# Part3_3210105209.net
KiCad netlist of a schematic drawn in Altium Designer
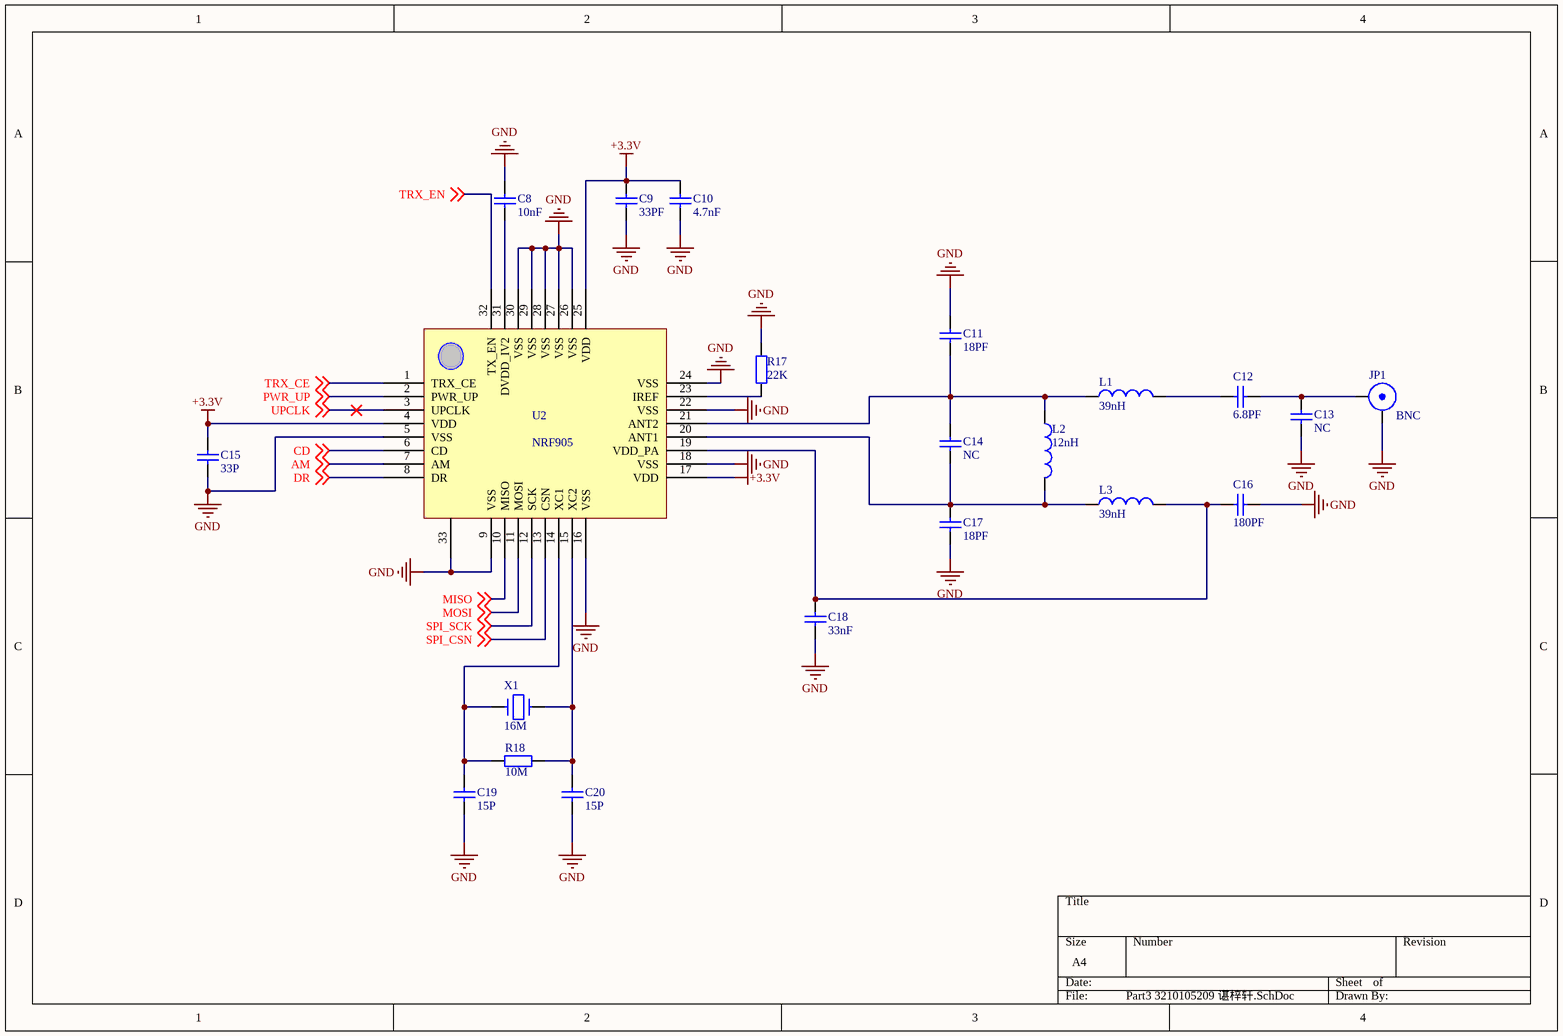
[diagram p0: Part3 3210105209 谌梓轩.SchDoc]

(export (version "E")
  (design (tool "Eeschema 10.0.6"))
  (components
    (comp (ref "C8")
      (value "10nF")
      (footprint "0603C")
      (description "Capacitor")
      (fields (field (name "PUBLISHER") "Altium Limited"))
      (libsource (lib "ECG2.0_1") (part "Cap"))
    )
    (comp (ref "C9")
      (value "33PF")
      (footprint "0603C")
      (description "Capacitor")
      (fields (field (name "PUBLISHER") "Altium Limited"))
      (libsource (lib "ECG2.0_1") (part "Cap"))
    )
    (comp (ref "C10")
      (value "4.7nF")
      (footprint "0603C")
      (description "Capacitor")
      (fields (field (name "PUBLISHER") "Altium Limited"))
      (libsource (lib "ECG2.0_1") (part "Cap"))
    )
    (comp (ref "C11")
      (value "18PF")
      (footprint "0603C")
      (description "Capacitor")
      (fields (field (name "PUBLISHER") "Altium Limited"))
      (libsource (lib "ECG2.0_1") (part "Cap"))
    )
    (comp (ref "C12")
      (value "6.8PF")
      (footprint "0603C")
      (description "Capacitor")
      (fields (field (name "PUBLISHER") "Altium Limited"))
      (libsource (lib "ECG2.0_1") (part "Cap"))
    )
    (comp (ref "C13")
      (value "NC")
      (footprint "0603C")
      (description "Capacitor")
      (fields (field (name "PUBLISHER") "Altium Limited"))
      (libsource (lib "ECG2.0_1") (part "Cap"))
    )
    (comp (ref "C14")
      (value "NC")
      (footprint "0603C")
      (description "Capacitor")
      (fields (field (name "PUBLISHER") "Altium Limited"))
      (libsource (lib "ECG2.0_1") (part "Cap"))
    )
    (comp (ref "C15")
      (value "33P")
      (footprint "0603C")
      (description "Capacitor")
      (fields (field (name "PUBLISHER") "Altium Limited"))
      (libsource (lib "ECG2.0_1") (part "Cap"))
    )
    (comp (ref "C16")
      (value "180PF")
      (footprint "0603C")
      (description "Capacitor")
      (fields (field (name "PUBLISHER") "Altium Limited"))
      (libsource (lib "ECG2.0_1") (part "Cap"))
    )
    (comp (ref "C17")
      (value "18PF")
      (footprint "0603C")
      (description "Capacitor")
      (fields (field (name "PUBLISHER") "Altium Limited"))
      (libsource (lib "ECG2.0_1") (part "Cap"))
    )
    (comp (ref "C18")
      (value "33nF")
      (footprint "0603C")
      (description "Capacitor")
      (fields (field (name "PUBLISHER") "Altium Limited"))
      (libsource (lib "ECG2.0_1") (part "Cap"))
    )
    (comp (ref "C19")
      (value "15P")
      (footprint "0603C")
      (description "Capacitor")
      (fields (field (name "PUBLISHER") "Altium Limited"))
      (libsource (lib "ECG2.0_1") (part "Cap"))
    )
    (comp (ref "C20")
      (value "15P")
      (footprint "0603C")
      (description "Capacitor")
      (fields (field (name "PUBLISHER") "Altium Limited"))
      (libsource (lib "ECG2.0_1") (part "Cap"))
    )
    (comp (ref "JP1") (value "BNC") (footprint "SMA") (libsource (lib "ECG2.0_1") (part "BNC")))
    (comp (ref "L1") (value "39nH") (footprint "0603-D") (libsource (lib "ECG2.0_1") (part "INDUCTOR")))
    (comp (ref "L2") (value "12nH") (footprint "0603-D") (libsource (lib "ECG2.0_1") (part "INDUCTOR")))
    (comp (ref "L3") (value "39nH") (footprint "0603-D") (libsource (lib "ECG2.0_1") (part "INDUCTOR")))
    (comp (ref "R17")
      (value "22K")
      (footprint "0603R")
      (description "Resistor")
      (fields (field (name "PUBLISHER") "Altium Limited"))
      (libsource (lib "ECG2.0_1") (part "Res2"))
    )
    (comp (ref "R18")
      (value "10M")
      (footprint "0603R")
      (description "Resistor")
      (fields (field (name "PUBLISHER") "Altium Limited"))
      (libsource (lib "") (part "Res2_1"))
    )
    (comp (ref "U2")
      (value "NRF905")
      (footprint "QFN32_M")
      (libsource (lib "ECG2.0_1") (part "Component_1_1"))
    )
    (comp (ref "X1") (value "16M") (footprint "CY2") (libsource (lib "ECG2.0_1") (part "CRYSTAL")))
  )
  (nets
    (net (code "1") (name "+3.3V") (class "Default")
      (node (ref "C10") (pin "2") (pinfunction "2_2") (pintype "passive"))
      (node (ref "C15") (pin "2") (pinfunction "2_2") (pintype "passive"))
      (node (ref "C9") (pin "2") (pinfunction "2_2") (pintype "passive"))
      (node (ref "U2") (pin "17") (pinfunction "VDD_17") (pintype "passive"))
      (node (ref "U2") (pin "25") (pinfunction "VDD_25") (pintype "passive"))
      (node (ref "U2") (pin "4") (pinfunction "VDD_4") (pintype "passive"))
    )
    (net (code "2") (name "AM") (class "Default")
      (node (ref "U2") (pin "7") (pinfunction "AM_7") (pintype "passive"))
    )
    (net (code "3") (name "CD") (class "Default")
      (node (ref "U2") (pin "6") (pinfunction "CD_6") (pintype "passive"))
    )
    (net (code "4") (name "DR") (class "Default")
      (node (ref "U2") (pin "8") (pinfunction "DR_8") (pintype "passive"))
    )
    (net (code "5") (name "GND") (class "Default")
      (node (ref "C10") (pin "1") (pinfunction "1_1") (pintype "passive"))
      (node (ref "C11") (pin "2") (pinfunction "2_2") (pintype "passive"))
      (node (ref "C13") (pin "1") (pinfunction "1_1") (pintype "passive"))
      (node (ref "C15") (pin "1") (pinfunction "1_1") (pintype "passive"))
      (node (ref "C16") (pin "2") (pinfunction "2_2") (pintype "passive"))
      (node (ref "C17") (pin "1") (pinfunction "1_1") (pintype "passive"))
      (node (ref "C18") (pin "1") (pinfunction "1_1") (pintype "passive"))
      (node (ref "C19") (pin "1") (pinfunction "1_1") (pintype "passive"))
      (node (ref "C20") (pin "1") (pinfunction "1_1") (pintype "passive"))
      (node (ref "C8") (pin "2") (pinfunction "2_2") (pintype "passive"))
      (node (ref "C9") (pin "1") (pinfunction "1_1") (pintype "passive"))
      (node (ref "JP1") (pin "1") (pintype "passive"))
      (node (ref "R17") (pin "2") (pinfunction "2_2") (pintype "passive"))
      (node (ref "U2") (pin "16") (pinfunction "VSS_16") (pintype "passive"))
      (node (ref "U2") (pin "18") (pinfunction "VSS_18") (pintype "passive"))
      (node (ref "U2") (pin "22") (pinfunction "VSS_22") (pintype "passive"))
      (node (ref "U2") (pin "24") (pinfunction "VSS_24") (pintype "passive"))
      (node (ref "U2") (pin "26") (pinfunction "VSS_26") (pintype "passive"))
      (node (ref "U2") (pin "27") (pinfunction "VSS_27") (pintype "passive"))
      (node (ref "U2") (pin "28") (pinfunction "VSS_28") (pintype "passive"))
      (node (ref "U2") (pin "29") (pinfunction "VSS_29") (pintype "passive"))
      (node (ref "U2") (pin "30") (pinfunction "VSS_30") (pintype "passive"))
      (node (ref "U2") (pin "33") (pinfunction "33_33") (pintype "passive"))
      (node (ref "U2") (pin "5") (pinfunction "VSS_5") (pintype "passive"))
      (node (ref "U2") (pin "9") (pinfunction "VSS_9") (pintype "passive"))
    )
    (net (code "6") (name "MISO") (class "Default")
      (node (ref "U2") (pin "10") (pinfunction "MISO_10") (pintype "passive"))
    )
    (net (code "7") (name "MOSI") (class "Default")
      (node (ref "U2") (pin "11") (pinfunction "MOSI_11") (pintype "passive"))
    )
    (net (code "8") (name "Net-(C12-Pad1)") (class "Default")
      (node (ref "C12") (pin "1") (pinfunction "1_1") (pintype "passive"))
      (node (ref "L1") (pin "2") (pinfunction "2_2") (pintype "passive"))
    )
    (net (code "9") (name "Net-(C12-Pad2)") (class "Default")
      (node (ref "C12") (pin "2") (pinfunction "2_2") (pintype "passive"))
      (node (ref "C13") (pin "2") (pinfunction "2_2") (pintype "passive"))
      (node (ref "JP1") (pin "2") (pintype "passive"))
    )
    (net (code "10") (name "Net-(U2-ANT1)") (class "Default")
      (node (ref "C14") (pin "1") (pinfunction "1_1") (pintype "passive"))
      (node (ref "C17") (pin "2") (pinfunction "2_2") (pintype "passive"))
      (node (ref "L2") (pin "2") (pinfunction "2_2") (pintype "passive"))
      (node (ref "L3") (pin "1") (pinfunction "1_1") (pintype "passive"))
      (node (ref "U2") (pin "20") (pinfunction "ANT1_20") (pintype "passive"))
    )
    (net (code "11") (name "Net-(U2-ANT2)") (class "Default")
      (node (ref "C11") (pin "1") (pinfunction "1_1") (pintype "passive"))
      (node (ref "C14") (pin "2") (pinfunction "2_2") (pintype "passive"))
      (node (ref "L1") (pin "1") (pinfunction "1_1") (pintype "passive"))
      (node (ref "L2") (pin "1") (pinfunction "1_1") (pintype "passive"))
      (node (ref "U2") (pin "21") (pinfunction "ANT2_21") (pintype "passive"))
    )
    (net (code "12") (name "Net-(U2-DVDD_IV2)") (class "Default")
      (node (ref "C8") (pin "1") (pinfunction "1_1") (pintype "passive"))
      (node (ref "U2") (pin "31") (pinfunction "DVDD_IV2_31") (pintype "passive"))
    )
    (net (code "13") (name "Net-(U2-IREF)") (class "Default")
      (node (ref "R17") (pin "1") (pinfunction "1_1") (pintype "passive"))
      (node (ref "U2") (pin "23") (pinfunction "IREF_23") (pintype "passive"))
    )
    (net (code "14") (name "Net-(U2-VDD_PA)") (class "Default")
      (node (ref "C16") (pin "1") (pinfunction "1_1") (pintype "passive"))
      (node (ref "C18") (pin "2") (pinfunction "2_2") (pintype "passive"))
      (node (ref "L3") (pin "2") (pinfunction "2_2") (pintype "passive"))
      (node (ref "U2") (pin "19") (pinfunction "VDD_PA_19") (pintype "passive"))
    )
    (net (code "15") (name "Net-(U2-XC1)") (class "Default")
      (node (ref "C19") (pin "2") (pinfunction "2_2") (pintype "passive"))
      (node (ref "R18") (pin "1") (pinfunction "1_1") (pintype "passive"))
      (node (ref "U2") (pin "14") (pinfunction "XC1_14") (pintype "passive"))
      (node (ref "X1") (pin "1") (pintype "passive"))
    )
    (net (code "16") (name "Net-(U2-XC2)") (class "Default")
      (node (ref "C20") (pin "2") (pinfunction "2_2") (pintype "passive"))
      (node (ref "R18") (pin "2") (pinfunction "2_2") (pintype "passive"))
      (node (ref "U2") (pin "15") (pinfunction "XC2_15") (pintype "passive"))
      (node (ref "X1") (pin "2") (pintype "passive"))
    )
    (net (code "17") (name "PWR_UP") (class "Default")
      (node (ref "U2") (pin "2") (pinfunction "PWR_UP_2") (pintype "passive"))
    )
    (net (code "18") (name "SPI_CSN") (class "Default")
      (node (ref "U2") (pin "13") (pinfunction "CSN_13") (pintype "passive"))
    )
    (net (code "19") (name "SPI_SCK") (class "Default")
      (node (ref "U2") (pin "12") (pinfunction "SCK_12") (pintype "passive"))
    )
    (net (code "20") (name "TRX_CE") (class "Default")
      (node (ref "U2") (pin "1") (pinfunction "TRX_CE_1") (pintype "passive"))
    )
    (net (code "21") (name "TRX_EN") (class "Default")
      (node (ref "U2") (pin "32") (pinfunction "TX_EN_32") (pintype "passive"))
    )
    (net (code "22") (name "UPCLK") (class "Default")
      (node (ref "U2") (pin "3") (pinfunction "UPCLK_3") (pintype "passive"))
    )
  )
)
